# Yaris_speed_door_lock-ext_power_and_rela.net
KiCad netlist of a schematic drawn in EAGLE
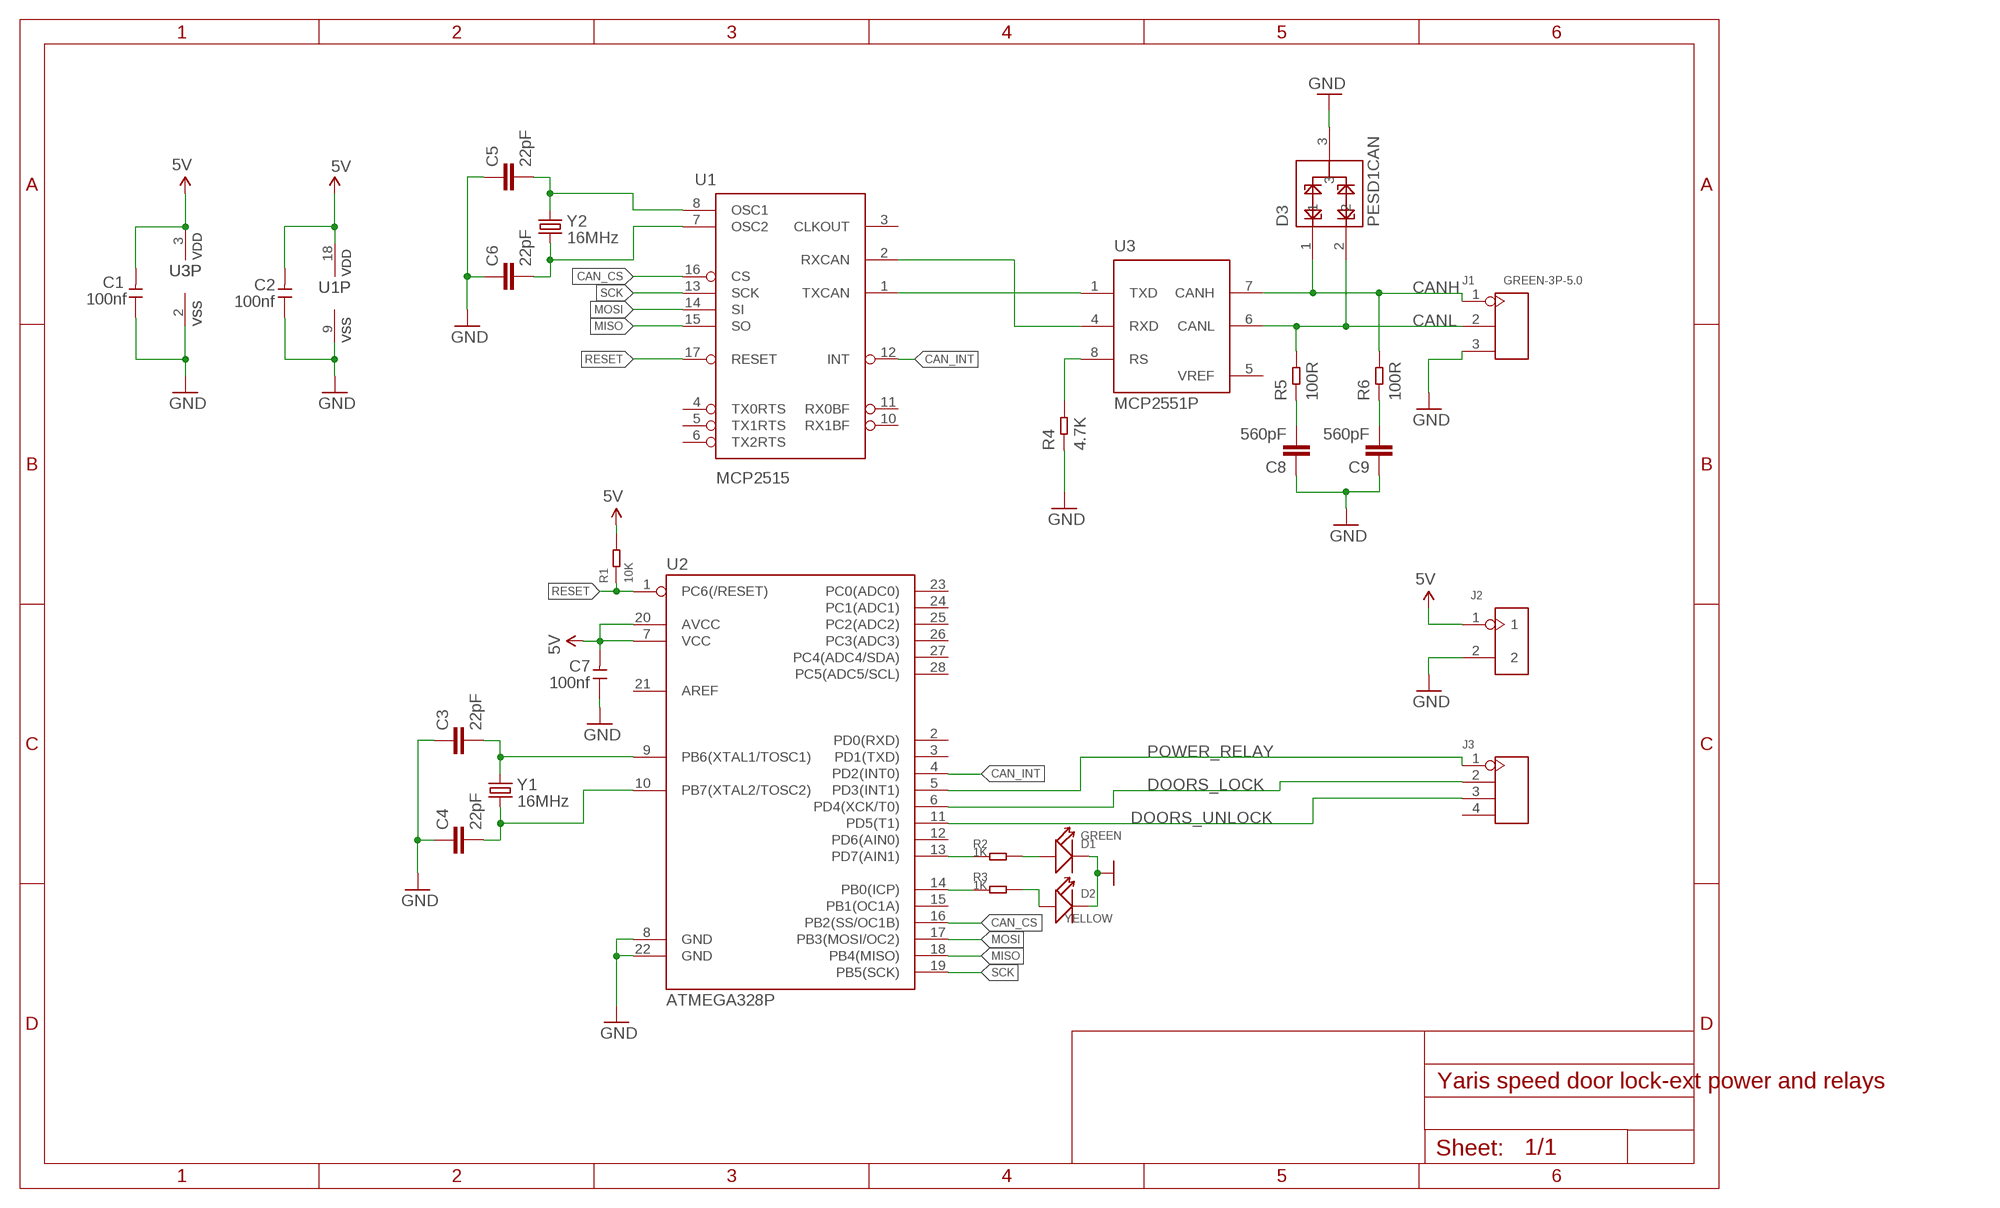
[diagram p0: schematic, sheet 1]

(export (version "E")
  (design (tool "Eeschema 10.0.6"))
  (components
    (comp (ref "C1")
      (value "100nf")
      (footprint "eagle-import:CERAMIC-2.54")
      (fields (field (name "MPN") "CC1-F5SL2A101KSPW"))
      (libsource (lib "eagle-import") (part "DIP-CERAMIC-DISC-100NF-50V-Y5V(D5.0MM)"))
    )
    (comp (ref "C2")
      (value "100nf")
      (footprint "eagle-import:CERAMIC-2.54")
      (fields (field (name "MPN") "CC1-F5SL2A101KSPW"))
      (libsource (lib "eagle-import") (part "DIP-CERAMIC-DISC-100NF-50V-Y5V(D5.0MM)"))
    )
    (comp (ref "C3")
      (value "22pF")
      (footprint "eagle-import:CAP-PTH-2.54")
      (libsource (lib "eagle-import") (part "22PF-PTH-2.54MM-200V-5%"))
    )
    (comp (ref "C4")
      (value "22pF")
      (footprint "eagle-import:CAP-PTH-2.54")
      (libsource (lib "eagle-import") (part "22PF-PTH-2.54MM-200V-5%"))
    )
    (comp (ref "C5")
      (value "22pF")
      (footprint "eagle-import:CAP-PTH-2.54")
      (libsource (lib "eagle-import") (part "22PF-PTH-2.54MM-200V-5%"))
    )
    (comp (ref "C6")
      (value "22pF")
      (footprint "eagle-import:CAP-PTH-2.54")
      (libsource (lib "eagle-import") (part "22PF-PTH-2.54MM-200V-5%"))
    )
    (comp (ref "C7")
      (value "100nf")
      (footprint "eagle-import:CERAMIC-2.54")
      (fields (field (name "MPN") "CC1-F5SL2A101KSPW"))
      (libsource (lib "eagle-import") (part "DIP-CERAMIC-DISC-100NF-50V-Y5V(D5.0MM)"))
    )
    (comp (ref "C8")
      (value "560pF")
      (footprint "eagle-import:0603-CAP")
      (libsource (lib "eagle-import") (part "560PF-50V-5%(0603)"))
    )
    (comp (ref "C9")
      (value "560pF")
      (footprint "eagle-import:0603-CAP")
      (libsource (lib "eagle-import") (part "560PF-50V-5%(0603)"))
    )
    (comp (ref "D1")
      (value "GREEN")
      (footprint "eagle-import:LED2-2.54-D3.0MM")
      (fields (field (name "MPN") "CX-G302DC"))
      (libsource (lib "eagle-import") (part "DIP-LED-GREEN-GREEN(2P-D3MM)"))
    )
    (comp (ref "D2")
      (value "YELLOW")
      (footprint "eagle-import:LED2-2.54-D3.0MM")
      (fields (field (name "MPN") "CX-G302DC"))
      (libsource (lib "eagle-import") (part "DIP-LED-GREEN-GREEN(2P-D3MM)"))
    )
    (comp (ref "D3")
      (value "PESD1CAN")
      (footprint "eagle-import:SOT23-3")
      (libsource (lib "eagle-import") (part "PESD1CAN"))
    )
    (comp (ref "J1")
      (value "GREEN-3P-5.0")
      (footprint "eagle-import:H3-5.0-15.5X8.0MM")
      (libsource (lib "eagle-import") (part "SCREW-TERMINAL-GREEN(3P-5.0)"))
    )
    (comp (ref "J2")
      (value "DIP-BLACK-JUMPER")
      (footprint "eagle-import:H2-2.54")
      (libsource (lib "eagle-import") (part "DIP-BLACK-JUMPER"))
    )
    (comp (ref "J3")
      (value "DIP-BLACK-FEMALE-HEADER-VERT(4P-2.54)")
      (footprint "eagle-import:H4-2.54")
      (fields (field (name "MPN") "F185-1104A1BSYA1"))
      (libsource (lib "eagle-import") (part "DIP-BLACK-FEMALE-HEADER-VERT(4P-2.54)"))
    )
    (comp (ref "R1")
      (value "10K")
      (footprint "eagle-import:PR-D2.3XL6.5MM")
      (fields (field (name "MPN") "FHCFR-1/4W-103J"))
      (libsource (lib "eagle-import") (part "DIP-RES-10K-5%-1/4W(PR-D2.3XL6.5MM)"))
    )
    (comp (ref "R2")
      (value "1K")
      (footprint "eagle-import:PR-D2.3XL6.5MM")
      (fields (field (name "MPN") "FHCFR-1/4W-102J"))
      (libsource (lib "eagle-import") (part "DIP-RES-1K-5%-1/4W(PR-D2.3XL6.5MM)"))
    )
    (comp (ref "R3")
      (value "1K")
      (footprint "eagle-import:PR-D2.3XL6.5MM")
      (fields (field (name "MPN") "FHCFR-1/4W-102J"))
      (libsource (lib "eagle-import") (part "DIP-RES-1K-5%-1/4W(PR-D2.3XL6.5MM)"))
    )
    (comp (ref "R4")
      (value "4.7K")
      (footprint "eagle-import:PR-D2.3XL6.5MM")
      (fields (field (name "MPN") "FHCFR-1/4W-472J"))
      (libsource (lib "eagle-import") (part "DIP-RES-4.7K-5%-1/4W(PR-D2.3XL6.5MM)"))
    )
    (comp (ref "R5")
      (value "100R")
      (footprint "eagle-import:PR-D2.3XL6.5MM")
      (fields (field (name "MPN") "FHCFR-1/4W-101J"))
      (libsource (lib "eagle-import") (part "DIP-RES-100R-5%-1/4W(PR-D2.3XL6.5MM)"))
    )
    (comp (ref "R6")
      (value "100R")
      (footprint "eagle-import:PR-D2.3XL6.5MM")
      (fields (field (name "MPN") "FHCFR-1/4W-101J"))
      (libsource (lib "eagle-import") (part "DIP-RES-100R-5%-1/4W(PR-D2.3XL6.5MM)"))
    )
    (comp (ref "U1")
      (value "MCP2515")
      (footprint "eagle-import:SO-18W")
      (libsource (lib "eagle-import") (part "MCP2510SO"))
    )
    (comp (ref "U2")
      (value "ATMEGA328P")
      (footprint "eagle-import:DIP28")
      (libsource (lib "eagle-import") (part "ATMEGA328P_PDIP"))
    )
    (comp (ref "U3")
      (value "MCP2551P")
      (footprint "eagle-import:DIL8")
      (libsource (lib "eagle-import") (part "MCP2551P"))
    )
    (comp (ref "Y1")
      (value "16MHz")
      (footprint "eagle-import:HC49US")
      (libsource (lib "eagle-import") (part "CRYSTALHC49US"))
    )
    (comp (ref "Y2")
      (value "16MHz")
      (footprint "eagle-import:HC49US")
      (libsource (lib "eagle-import") (part "CRYSTALHC49US"))
    )
  )
  (nets
    (net (code "1") (name "/CANH") (class "Default")
      (node (ref "D3") (pin "1") (pinfunction "1_1") (pintype "bidirectional"))
      (node (ref "J1") (pin "1") (pinfunction "P$1_1") (pintype "bidirectional"))
      (node (ref "R6") (pin "2") (pinfunction "2_2") (pintype "passive"))
      (node (ref "U3") (pin "7") (pinfunction "CANH_7") (pintype "bidirectional"))
    )
    (net (code "2") (name "/CANL") (class "Default")
      (node (ref "D3") (pin "2") (pinfunction "2_2") (pintype "bidirectional"))
      (node (ref "J1") (pin "2") (pinfunction "P$2_2") (pintype "bidirectional"))
      (node (ref "R5") (pin "2") (pinfunction "2_2") (pintype "passive"))
      (node (ref "U3") (pin "6") (pinfunction "CANL_6") (pintype "bidirectional"))
    )
    (net (code "3") (name "/DOORS_LOCK") (class "Default")
      (node (ref "J3") (pin "2") (pinfunction "P$2_2") (pintype "bidirectional"))
      (node (ref "U2") (pin "6") (pinfunction "PD4(XCK/T0)_6") (pintype "bidirectional"))
    )
    (net (code "4") (name "/DOORS_UNLOCK") (class "Default")
      (node (ref "J3") (pin "3") (pinfunction "P$3_3") (pintype "bidirectional"))
      (node (ref "U2") (pin "11") (pinfunction "PD5(T1)_11") (pintype "bidirectional"))
    )
    (net (code "5") (name "/POWER_RELAY") (class "Default")
      (node (ref "J3") (pin "1") (pinfunction "P$1_1") (pintype "bidirectional"))
      (node (ref "U2") (pin "5") (pinfunction "PD3(INT1)_5") (pintype "bidirectional"))
    )
    (net (code "6") (name "/VREF") (class "Default")
      (node (ref "U3") (pin "5") (pinfunction "VREF_5") (pintype "power_in"))
    )
    (net (code "7") (name "5V") (class "Default")
      (node (ref "C1") (pin "2") (pinfunction "2_2") (pintype "passive"))
      (node (ref "C2") (pin "2") (pinfunction "2_2") (pintype "passive"))
      (node (ref "C7") (pin "2") (pinfunction "2_2") (pintype "passive"))
      (node (ref "J2") (pin "1") (pinfunction "1_1") (pintype "bidirectional"))
      (node (ref "R1") (pin "2") (pinfunction "2_2") (pintype "passive"))
      (node (ref "U1") (pin "18") (pinfunction "VDD_18") (pintype "power_in"))
      (node (ref "U2") (pin "20") (pinfunction "AVCC_20") (pintype "bidirectional"))
      (node (ref "U2") (pin "7") (pinfunction "VCC_7") (pintype "bidirectional"))
      (node (ref "U3") (pin "3") (pinfunction "VDD_3") (pintype "power_in"))
    )
    (net (code "8") (name "CAN_CS") (class "Default")
      (node (ref "U1") (pin "16") (pinfunction "CS_16") (pintype "input"))
      (node (ref "U2") (pin "16") (pinfunction "PB2(SS/OC1B)_16") (pintype "bidirectional"))
    )
    (net (code "9") (name "CAN_INT") (class "Default")
      (node (ref "U1") (pin "12") (pinfunction "INT_12") (pintype "output"))
      (node (ref "U2") (pin "4") (pinfunction "PD2(INT0)_4") (pintype "bidirectional"))
    )
    (net (code "10") (name "GND") (class "Default")
      (node (ref "C1") (pin "1") (pinfunction "1_1") (pintype "passive"))
      (node (ref "C2") (pin "1") (pinfunction "1_1") (pintype "passive"))
      (node (ref "C3") (pin "1") (pinfunction "1_1") (pintype "passive"))
      (node (ref "C4") (pin "1") (pinfunction "1_1") (pintype "passive"))
      (node (ref "C5") (pin "1") (pinfunction "1_1") (pintype "passive"))
      (node (ref "C6") (pin "1") (pinfunction "1_1") (pintype "passive"))
      (node (ref "C7") (pin "1") (pinfunction "1_1") (pintype "passive"))
      (node (ref "C8") (pin "1") (pinfunction "1_1") (pintype "passive"))
      (node (ref "C9") (pin "1") (pinfunction "1_1") (pintype "passive"))
      (node (ref "D1") (pin "K") (pinfunction "-_K") (pintype "passive"))
      (node (ref "D2") (pin "K") (pinfunction "-_K") (pintype "passive"))
      (node (ref "D3") (pin "3") (pinfunction "3_3") (pintype "bidirectional"))
      (node (ref "J1") (pin "3") (pinfunction "P$3_3") (pintype "bidirectional"))
      (node (ref "J2") (pin "2") (pinfunction "2_2") (pintype "bidirectional"))
      (node (ref "R4") (pin "1") (pinfunction "1_1") (pintype "passive"))
      (node (ref "U1") (pin "9") (pinfunction "VSS_9") (pintype "power_in"))
      (node (ref "U2") (pin "22") (pinfunction "GND_22") (pintype "bidirectional"))
      (node (ref "U2") (pin "8") (pinfunction "GND_8") (pintype "bidirectional"))
      (node (ref "U3") (pin "2") (pinfunction "VSS_2") (pintype "power_in"))
    )
    (net (code "11") (name "MISO") (class "Default")
      (node (ref "U1") (pin "15") (pinfunction "SO_15") (pintype "output"))
      (node (ref "U2") (pin "18") (pinfunction "PB4(MISO)_18") (pintype "bidirectional"))
    )
    (net (code "12") (name "MOSI") (class "Default")
      (node (ref "U1") (pin "14") (pinfunction "SI_14") (pintype "input"))
      (node (ref "U2") (pin "17") (pinfunction "PB3(MOSI/OC2)_17") (pintype "bidirectional"))
    )
    (net (code "13") (name "Net-(C8-Pad2)") (class "Default")
      (node (ref "C8") (pin "2") (pinfunction "2_2") (pintype "passive"))
      (node (ref "R5") (pin "1") (pinfunction "1_1") (pintype "passive"))
    )
    (net (code "14") (name "Net-(C9-Pad2)") (class "Default")
      (node (ref "C9") (pin "2") (pinfunction "2_2") (pintype "passive"))
      (node (ref "R6") (pin "1") (pinfunction "1_1") (pintype "passive"))
    )
    (net (code "15") (name "Net-(D1-+)") (class "Default")
      (node (ref "D1") (pin "A") (pinfunction "+_A") (pintype "passive"))
      (node (ref "R2") (pin "2") (pinfunction "2_2") (pintype "passive"))
    )
    (net (code "16") (name "Net-(D2-+)") (class "Default")
      (node (ref "D2") (pin "A") (pinfunction "+_A") (pintype "passive"))
      (node (ref "R3") (pin "2") (pinfunction "2_2") (pintype "passive"))
    )
    (net (code "17") (name "Net-(U1A-OSC1)") (class "Default")
      (node (ref "C5") (pin "2") (pinfunction "2_2") (pintype "passive"))
      (node (ref "U1") (pin "8") (pinfunction "OSC1_8") (pintype "input"))
      (node (ref "Y2") (pin "2") (pinfunction "2_2") (pintype "passive"))
    )
    (net (code "18") (name "Net-(U1A-OSC2)") (class "Default")
      (node (ref "C6") (pin "2") (pinfunction "2_2") (pintype "passive"))
      (node (ref "U1") (pin "7") (pinfunction "OSC2_7") (pintype "output"))
      (node (ref "Y2") (pin "1") (pinfunction "1_1") (pintype "passive"))
    )
    (net (code "19") (name "Net-(U1A-RXCAN)") (class "Default")
      (node (ref "U1") (pin "2") (pinfunction "RXCAN_2") (pintype "input"))
      (node (ref "U3") (pin "4") (pinfunction "RXD_4") (pintype "output"))
    )
    (net (code "20") (name "Net-(U1A-TXCAN)") (class "Default")
      (node (ref "U1") (pin "1") (pinfunction "TXCAN_1") (pintype "output"))
      (node (ref "U3") (pin "1") (pinfunction "TXD_1") (pintype "input"))
    )
    (net (code "21") (name "Net-(U2-PB0(ICP))") (class "Default")
      (node (ref "R3") (pin "1") (pinfunction "1_1") (pintype "passive"))
      (node (ref "U2") (pin "14") (pinfunction "PB0(ICP)_14") (pintype "bidirectional"))
    )
    (net (code "22") (name "Net-(U2-PB6(XTAL1{slash}TOSC1))") (class "Default")
      (node (ref "C3") (pin "2") (pinfunction "2_2") (pintype "passive"))
      (node (ref "U2") (pin "9") (pinfunction "PB6(XTAL1/TOSC1)_9") (pintype "bidirectional"))
      (node (ref "Y1") (pin "2") (pinfunction "2_2") (pintype "passive"))
    )
    (net (code "23") (name "Net-(U2-PB7(XTAL2{slash}TOSC2))") (class "Default")
      (node (ref "C4") (pin "2") (pinfunction "2_2") (pintype "passive"))
      (node (ref "U2") (pin "10") (pinfunction "PB7(XTAL2/TOSC2)_10") (pintype "bidirectional"))
      (node (ref "Y1") (pin "1") (pinfunction "1_1") (pintype "passive"))
    )
    (net (code "24") (name "Net-(U2-PD7(AIN1))") (class "Default")
      (node (ref "R2") (pin "1") (pinfunction "1_1") (pintype "passive"))
      (node (ref "U2") (pin "13") (pinfunction "PD7(AIN1)_13") (pintype "bidirectional"))
    )
    (net (code "25") (name "Net-(U3A-RS)") (class "Default")
      (node (ref "R4") (pin "2") (pinfunction "2_2") (pintype "passive"))
      (node (ref "U3") (pin "8") (pinfunction "RS_8") (pintype "input"))
    )
    (net (code "26") (name "RESET") (class "Default")
      (node (ref "R1") (pin "1") (pinfunction "1_1") (pintype "passive"))
      (node (ref "U1") (pin "17") (pinfunction "RESET_17") (pintype "input"))
      (node (ref "U2") (pin "1") (pinfunction "PC6(/RESET)_1") (pintype "bidirectional"))
    )
    (net (code "27") (name "SCK") (class "Default")
      (node (ref "U1") (pin "13") (pinfunction "SCK_13") (pintype "input"))
      (node (ref "U2") (pin "19") (pinfunction "PB5(SCK)_19") (pintype "bidirectional"))
    )
    (net (code "28") (name "unconnected-(J3-P$4-Pad4)") (class "Default")
      (node (ref "J3") (pin "4") (pinfunction "P$4_4") (pintype "bidirectional"))
    )
    (net (code "29") (name "unconnected-(U1A-CLKOUT-Pad3)") (class "Default")
      (node (ref "U1") (pin "3") (pinfunction "CLKOUT_3") (pintype "output"))
    )
    (net (code "30") (name "unconnected-(U1A-RX0BF-Pad11)") (class "Default")
      (node (ref "U1") (pin "11") (pinfunction "RX0BF_11") (pintype "output"))
    )
    (net (code "31") (name "unconnected-(U1A-RX1BF-Pad10)") (class "Default")
      (node (ref "U1") (pin "10") (pinfunction "RX1BF_10") (pintype "output"))
    )
    (net (code "32") (name "unconnected-(U1A-TX0RTS-Pad4)") (class "Default")
      (node (ref "U1") (pin "4") (pinfunction "TX0RTS_4") (pintype "input"))
    )
    (net (code "33") (name "unconnected-(U1A-TX1RTS-Pad5)") (class "Default")
      (node (ref "U1") (pin "5") (pinfunction "TX1RTS_5") (pintype "input"))
    )
    (net (code "34") (name "unconnected-(U1A-TX2RTS-Pad6)") (class "Default")
      (node (ref "U1") (pin "6") (pinfunction "TX2RTS_6") (pintype "input"))
    )
    (net (code "35") (name "unconnected-(U2-AREF-Pad21)") (class "Default")
      (node (ref "U2") (pin "21") (pinfunction "AREF_21") (pintype "bidirectional"))
    )
    (net (code "36") (name "unconnected-(U2-PB1(OC1A)-Pad15)") (class "Default")
      (node (ref "U2") (pin "15") (pinfunction "PB1(OC1A)_15") (pintype "bidirectional"))
    )
    (net (code "37") (name "unconnected-(U2-PC0(ADC0)-Pad23)") (class "Default")
      (node (ref "U2") (pin "23") (pinfunction "PC0(ADC0)_23") (pintype "bidirectional"))
    )
    (net (code "38") (name "unconnected-(U2-PC1(ADC1)-Pad24)") (class "Default")
      (node (ref "U2") (pin "24") (pinfunction "PC1(ADC1)_24") (pintype "bidirectional"))
    )
    (net (code "39") (name "unconnected-(U2-PC2(ADC2)-Pad25)") (class "Default")
      (node (ref "U2") (pin "25") (pinfunction "PC2(ADC2)_25") (pintype "bidirectional"))
    )
    (net (code "40") (name "unconnected-(U2-PC3(ADC3)-Pad26)") (class "Default")
      (node (ref "U2") (pin "26") (pinfunction "PC3(ADC3)_26") (pintype "bidirectional"))
    )
    (net (code "41") (name "unconnected-(U2-PC4(ADC4{slash}SDA)-Pad27)") (class "Default")
      (node (ref "U2") (pin "27") (pinfunction "PC4(ADC4/SDA)_27") (pintype "bidirectional"))
    )
    (net (code "42") (name "unconnected-(U2-PC5(ADC5{slash}SCL)-Pad28)") (class "Default")
      (node (ref "U2") (pin "28") (pinfunction "PC5(ADC5/SCL)_28") (pintype "bidirectional"))
    )
    (net (code "43") (name "unconnected-(U2-PD0(RXD)-Pad2)") (class "Default")
      (node (ref "U2") (pin "2") (pinfunction "PD0(RXD)_2") (pintype "bidirectional"))
    )
    (net (code "44") (name "unconnected-(U2-PD1(TXD)-Pad3)") (class "Default")
      (node (ref "U2") (pin "3") (pinfunction "PD1(TXD)_3") (pintype "bidirectional"))
    )
    (net (code "45") (name "unconnected-(U2-PD6(AIN0)-Pad12)") (class "Default")
      (node (ref "U2") (pin "12") (pinfunction "PD6(AIN0)_12") (pintype "bidirectional"))
    )
  )
)
